# 7segment_multiplex.net
KiCad netlist of a schematic drawn in EAGLE
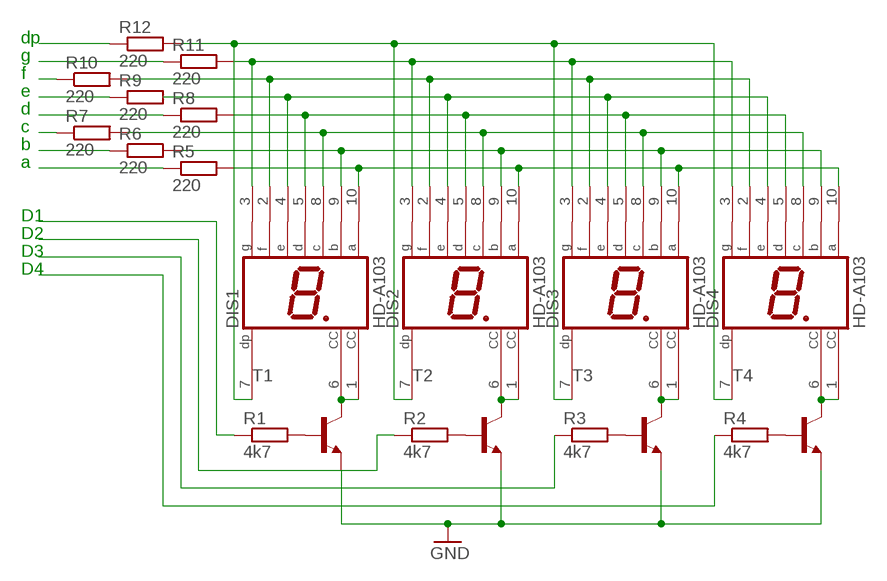
[diagram p0: schematic, sheet 1]

(export (version "E")
  (design (tool "Eeschema 10.0.6"))
  (components
    (comp (ref "DIS1")
      (value "HD-A103")
      (footprint "eagle-import:HDSP-A")
      (libsource (lib "eagle-import") (part "HD-A103"))
    )
    (comp (ref "DIS2")
      (value "HD-A103")
      (footprint "eagle-import:HDSP-A")
      (libsource (lib "eagle-import") (part "HD-A103"))
    )
    (comp (ref "DIS3")
      (value "HD-A103")
      (footprint "eagle-import:HDSP-A")
      (libsource (lib "eagle-import") (part "HD-A103"))
    )
    (comp (ref "DIS4")
      (value "HD-A103")
      (footprint "eagle-import:HDSP-A")
      (libsource (lib "eagle-import") (part "HD-A103"))
    )
    (comp (ref "R1")
      (value "4k7")
      (footprint "eagle-import:0204_7")
      (libsource (lib "eagle-import") (part "R-EU_0204/7"))
    )
    (comp (ref "R2")
      (value "4k7")
      (footprint "eagle-import:0204_7")
      (libsource (lib "eagle-import") (part "R-EU_0204/7"))
    )
    (comp (ref "R3")
      (value "4k7")
      (footprint "eagle-import:0204_7")
      (libsource (lib "eagle-import") (part "R-EU_0204/7"))
    )
    (comp (ref "R4")
      (value "4k7")
      (footprint "eagle-import:0204_7")
      (libsource (lib "eagle-import") (part "R-EU_0204/7"))
    )
    (comp (ref "R5")
      (value "220")
      (footprint "eagle-import:0204_7")
      (libsource (lib "eagle-import") (part "R-EU_0204/7"))
    )
    (comp (ref "R6")
      (value "220")
      (footprint "eagle-import:0204_7")
      (libsource (lib "eagle-import") (part "R-EU_0204/7"))
    )
    (comp (ref "R7")
      (value "220")
      (footprint "eagle-import:0204_7")
      (libsource (lib "eagle-import") (part "R-EU_0204/7"))
    )
    (comp (ref "R8")
      (value "220")
      (footprint "eagle-import:0204_7")
      (libsource (lib "eagle-import") (part "R-EU_0204/7"))
    )
    (comp (ref "R9")
      (value "220")
      (footprint "eagle-import:0204_7")
      (libsource (lib "eagle-import") (part "R-EU_0204/7"))
    )
    (comp (ref "R10")
      (value "220")
      (footprint "eagle-import:0204_7")
      (libsource (lib "eagle-import") (part "R-EU_0204/7"))
    )
    (comp (ref "R11")
      (value "220")
      (footprint "eagle-import:0204_7")
      (libsource (lib "eagle-import") (part "R-EU_0204/7"))
    )
    (comp (ref "R12")
      (value "220")
      (footprint "eagle-import:0204_7")
      (libsource (lib "eagle-import") (part "R-EU_0204/7"))
    )
    (comp (ref "T1")
      (value "-NPN-TO92")
      (footprint "eagle-import:TO92")
      (libsource (lib "eagle-import") (part "-NPN-TO92"))
    )
    (comp (ref "T2")
      (value "-NPN-TO92")
      (footprint "eagle-import:TO92")
      (libsource (lib "eagle-import") (part "-NPN-TO92"))
    )
    (comp (ref "T3")
      (value "-NPN-TO92")
      (footprint "eagle-import:TO92")
      (libsource (lib "eagle-import") (part "-NPN-TO92"))
    )
    (comp (ref "T4")
      (value "-NPN-TO92")
      (footprint "eagle-import:TO92")
      (libsource (lib "eagle-import") (part "-NPN-TO92"))
    )
  )
  (nets
    (net (code "1") (name "GND") (class "Default")
      (node (ref "T1") (pin "1") (pinfunction "E_1") (pintype "passive"))
      (node (ref "T2") (pin "1") (pinfunction "E_1") (pintype "passive"))
      (node (ref "T3") (pin "1") (pinfunction "E_1") (pintype "passive"))
      (node (ref "T4") (pin "1") (pinfunction "E_1") (pintype "passive"))
    )
    (net (code "2") (name "Net-(DIS1-A)") (class "Default")
      (node (ref "DIS1") (pin "10") (pinfunction "A_10") (pintype "passive"))
      (node (ref "DIS2") (pin "10") (pinfunction "A_10") (pintype "passive"))
      (node (ref "DIS3") (pin "10") (pinfunction "A_10") (pintype "passive"))
      (node (ref "DIS4") (pin "10") (pinfunction "A_10") (pintype "passive"))
      (node (ref "R5") (pin "2") (pinfunction "2_2") (pintype "passive"))
    )
    (net (code "3") (name "Net-(DIS1-B)") (class "Default")
      (node (ref "DIS1") (pin "9") (pinfunction "B_9") (pintype "passive"))
      (node (ref "DIS2") (pin "9") (pinfunction "B_9") (pintype "passive"))
      (node (ref "DIS3") (pin "9") (pinfunction "B_9") (pintype "passive"))
      (node (ref "DIS4") (pin "9") (pinfunction "B_9") (pintype "passive"))
      (node (ref "R6") (pin "2") (pinfunction "2_2") (pintype "passive"))
    )
    (net (code "4") (name "Net-(DIS1-C)") (class "Default")
      (node (ref "DIS1") (pin "8") (pinfunction "C_8") (pintype "passive"))
      (node (ref "DIS2") (pin "8") (pinfunction "C_8") (pintype "passive"))
      (node (ref "DIS3") (pin "8") (pinfunction "C_8") (pintype "passive"))
      (node (ref "DIS4") (pin "8") (pinfunction "C_8") (pintype "passive"))
      (node (ref "R7") (pin "2") (pinfunction "2_2") (pintype "passive"))
    )
    (net (code "5") (name "Net-(DIS1-D)") (class "Default")
      (node (ref "DIS1") (pin "5") (pinfunction "D_5") (pintype "passive"))
      (node (ref "DIS2") (pin "5") (pinfunction "D_5") (pintype "passive"))
      (node (ref "DIS3") (pin "5") (pinfunction "D_5") (pintype "passive"))
      (node (ref "DIS4") (pin "5") (pinfunction "D_5") (pintype "passive"))
      (node (ref "R8") (pin "2") (pinfunction "2_2") (pintype "passive"))
    )
    (net (code "6") (name "Net-(DIS1-DP)") (class "Default")
      (node (ref "DIS1") (pin "7") (pinfunction "DP_7") (pintype "passive"))
      (node (ref "DIS2") (pin "7") (pinfunction "DP_7") (pintype "passive"))
      (node (ref "DIS3") (pin "7") (pinfunction "DP_7") (pintype "passive"))
      (node (ref "DIS4") (pin "7") (pinfunction "DP_7") (pintype "passive"))
      (node (ref "R12") (pin "2") (pinfunction "2_2") (pintype "passive"))
    )
    (net (code "7") (name "Net-(DIS1-E)") (class "Default")
      (node (ref "DIS1") (pin "4") (pinfunction "E_4") (pintype "passive"))
      (node (ref "DIS2") (pin "4") (pinfunction "E_4") (pintype "passive"))
      (node (ref "DIS3") (pin "4") (pinfunction "E_4") (pintype "passive"))
      (node (ref "DIS4") (pin "4") (pinfunction "E_4") (pintype "passive"))
      (node (ref "R9") (pin "2") (pinfunction "2_2") (pintype "passive"))
    )
    (net (code "8") (name "Net-(DIS1-F)") (class "Default")
      (node (ref "DIS1") (pin "2") (pinfunction "F_2") (pintype "passive"))
      (node (ref "DIS2") (pin "2") (pinfunction "F_2") (pintype "passive"))
      (node (ref "DIS3") (pin "2") (pinfunction "F_2") (pintype "passive"))
      (node (ref "DIS4") (pin "2") (pinfunction "F_2") (pintype "passive"))
      (node (ref "R10") (pin "2") (pinfunction "2_2") (pintype "passive"))
    )
    (net (code "9") (name "Net-(DIS1-G)") (class "Default")
      (node (ref "DIS1") (pin "3") (pinfunction "G_3") (pintype "passive"))
      (node (ref "DIS2") (pin "3") (pinfunction "G_3") (pintype "passive"))
      (node (ref "DIS3") (pin "3") (pinfunction "G_3") (pintype "passive"))
      (node (ref "DIS4") (pin "3") (pinfunction "G_3") (pintype "passive"))
      (node (ref "R11") (pin "2") (pinfunction "2_2") (pintype "passive"))
    )
    (net (code "10") (name "Net-(T1-B)") (class "Default")
      (node (ref "R1") (pin "2") (pinfunction "2_2") (pintype "passive"))
      (node (ref "T1") (pin "2") (pinfunction "B_2") (pintype "passive"))
    )
    (net (code "11") (name "Net-(T1-C)") (class "Default")
      (node (ref "DIS1") (pin "1") (pinfunction "CC_1") (pintype "passive"))
      (node (ref "DIS1") (pin "6") (pinfunction "CC_6") (pintype "passive"))
      (node (ref "T1") (pin "3") (pinfunction "C_3") (pintype "passive"))
    )
    (net (code "12") (name "Net-(T2-B)") (class "Default")
      (node (ref "R2") (pin "2") (pinfunction "2_2") (pintype "passive"))
      (node (ref "T2") (pin "2") (pinfunction "B_2") (pintype "passive"))
    )
    (net (code "13") (name "Net-(T2-C)") (class "Default")
      (node (ref "DIS2") (pin "1") (pinfunction "CC_1") (pintype "passive"))
      (node (ref "DIS2") (pin "6") (pinfunction "CC_6") (pintype "passive"))
      (node (ref "T2") (pin "3") (pinfunction "C_3") (pintype "passive"))
    )
    (net (code "14") (name "Net-(T3-B)") (class "Default")
      (node (ref "R3") (pin "2") (pinfunction "2_2") (pintype "passive"))
      (node (ref "T3") (pin "2") (pinfunction "B_2") (pintype "passive"))
    )
    (net (code "15") (name "Net-(T3-C)") (class "Default")
      (node (ref "DIS3") (pin "1") (pinfunction "CC_1") (pintype "passive"))
      (node (ref "DIS3") (pin "6") (pinfunction "CC_6") (pintype "passive"))
      (node (ref "T3") (pin "3") (pinfunction "C_3") (pintype "passive"))
    )
    (net (code "16") (name "Net-(T4-B)") (class "Default")
      (node (ref "R4") (pin "2") (pinfunction "2_2") (pintype "passive"))
      (node (ref "T4") (pin "2") (pinfunction "B_2") (pintype "passive"))
    )
    (net (code "17") (name "Net-(T4-C)") (class "Default")
      (node (ref "DIS4") (pin "1") (pinfunction "CC_1") (pintype "passive"))
      (node (ref "DIS4") (pin "6") (pinfunction "CC_6") (pintype "passive"))
      (node (ref "T4") (pin "3") (pinfunction "C_3") (pintype "passive"))
    )
    (net (code "18") (name "unconnected-(R1-Pad1)") (class "Default")
      (node (ref "R1") (pin "1") (pinfunction "1_1") (pintype "passive"))
    )
    (net (code "19") (name "unconnected-(R2-Pad1)") (class "Default")
      (node (ref "R2") (pin "1") (pinfunction "1_1") (pintype "passive"))
    )
    (net (code "20") (name "unconnected-(R3-Pad1)") (class "Default")
      (node (ref "R3") (pin "1") (pinfunction "1_1") (pintype "passive"))
    )
    (net (code "21") (name "unconnected-(R4-Pad1)") (class "Default")
      (node (ref "R4") (pin "1") (pinfunction "1_1") (pintype "passive"))
    )
    (net (code "22") (name "unconnected-(R5-Pad1)") (class "Default")
      (node (ref "R5") (pin "1") (pinfunction "1_1") (pintype "passive"))
    )
    (net (code "23") (name "unconnected-(R6-Pad1)") (class "Default")
      (node (ref "R6") (pin "1") (pinfunction "1_1") (pintype "passive"))
    )
    (net (code "24") (name "unconnected-(R7-Pad1)") (class "Default")
      (node (ref "R7") (pin "1") (pinfunction "1_1") (pintype "passive"))
    )
    (net (code "25") (name "unconnected-(R8-Pad1)") (class "Default")
      (node (ref "R8") (pin "1") (pinfunction "1_1") (pintype "passive"))
    )
    (net (code "26") (name "unconnected-(R9-Pad1)") (class "Default")
      (node (ref "R9") (pin "1") (pinfunction "1_1") (pintype "passive"))
    )
    (net (code "27") (name "unconnected-(R10-Pad1)") (class "Default")
      (node (ref "R10") (pin "1") (pinfunction "1_1") (pintype "passive"))
    )
    (net (code "28") (name "unconnected-(R11-Pad1)") (class "Default")
      (node (ref "R11") (pin "1") (pinfunction "1_1") (pintype "passive"))
    )
    (net (code "29") (name "unconnected-(R12-Pad1)") (class "Default")
      (node (ref "R12") (pin "1") (pinfunction "1_1") (pintype "passive"))
    )
  )
)
